# Rev_A.net
KiCad netlist of a schematic drawn in EAGLE
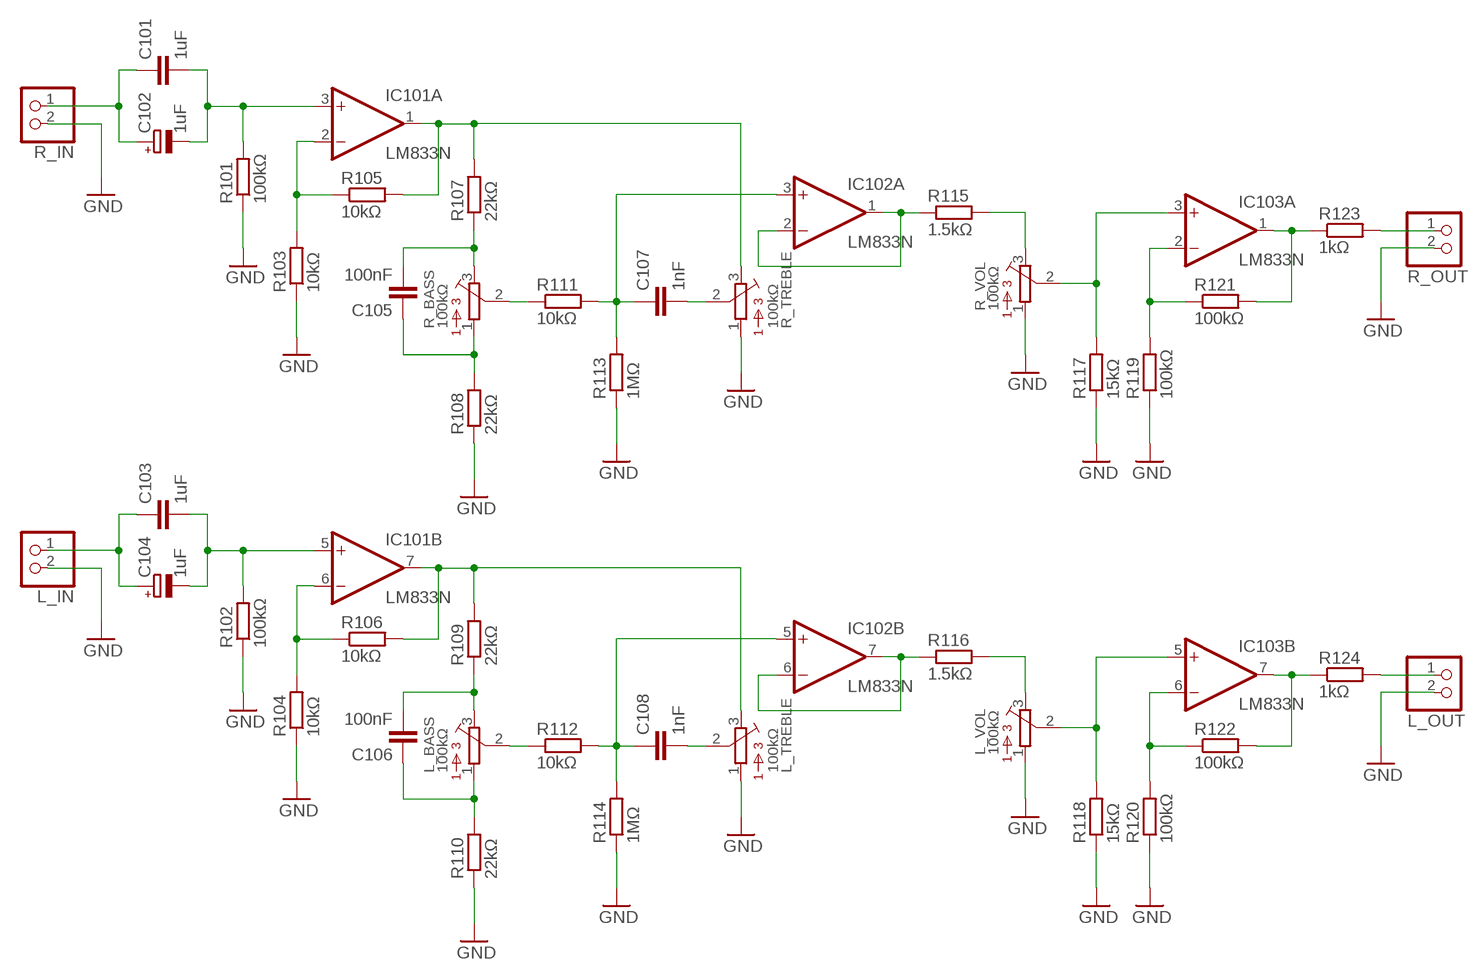
[diagram p0: schematic, sheet 1]
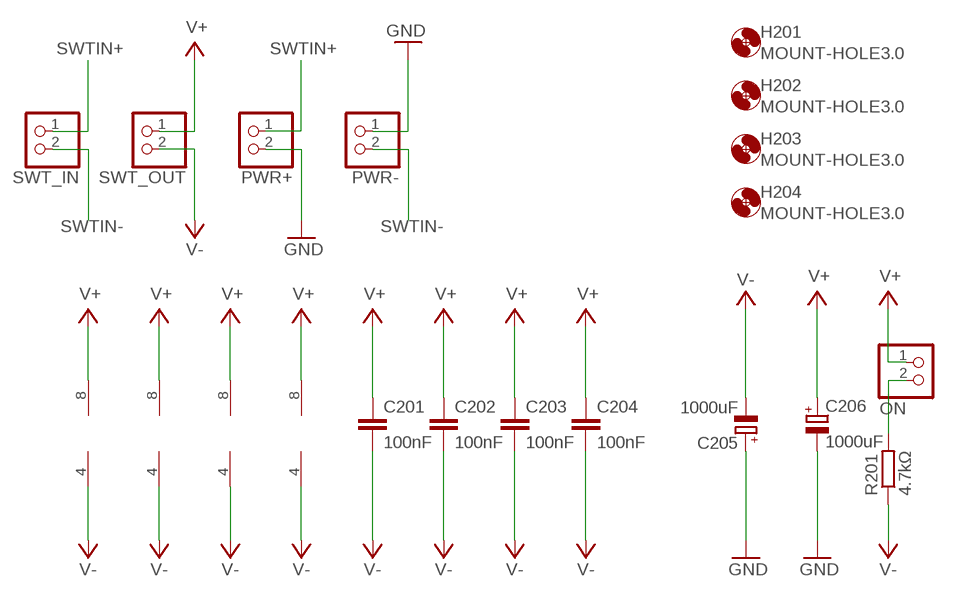
[diagram p1: schematic, sheet 2]
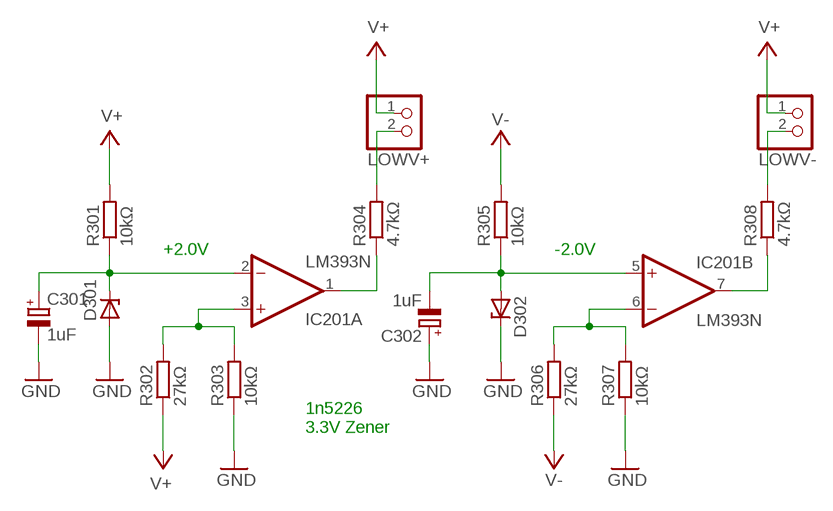
[diagram p2: schematic, sheet 3]

(export (version "E")
  (design (tool "Eeschema 10.0.6"))
  (components
    (comp (ref "C101")
      (value "1uF")
      (footprint "eagle-import:C150-072X183")
      (libsource (lib "eagle-import") (part "C-EU150-072X183"))
    )
    (comp (ref "C102")
      (value "1uF")
      (footprint "eagle-import:E2-5")
      (libsource (lib "eagle-import") (part "CPOL-EUE2-5"))
    )
    (comp (ref "C103")
      (value "1uF")
      (footprint "eagle-import:C150-072X183")
      (libsource (lib "eagle-import") (part "C-EU150-072X183"))
    )
    (comp (ref "C104")
      (value "1uF")
      (footprint "eagle-import:E2-5")
      (libsource (lib "eagle-import") (part "CPOL-EUE2-5"))
    )
    (comp (ref "C105")
      (value "100nF")
      (footprint "eagle-import:C050-025X075")
      (libsource (lib "eagle-import") (part "C-EU050-025X075"))
    )
    (comp (ref "C106")
      (value "100nF")
      (footprint "eagle-import:C050-025X075")
      (libsource (lib "eagle-import") (part "C-EU050-025X075"))
    )
    (comp (ref "C107")
      (value "1nF")
      (footprint "eagle-import:C050-025X075")
      (libsource (lib "eagle-import") (part "C-EU050-025X075"))
    )
    (comp (ref "C108")
      (value "1nF")
      (footprint "eagle-import:C050-025X075")
      (libsource (lib "eagle-import") (part "C-EU050-025X075"))
    )
    (comp (ref "IC101")
      (value "LM833N")
      (footprint "eagle-import:DIL08")
      (libsource (lib "eagle-import") (part "LM833N"))
    )
    (comp (ref "IC102")
      (value "LM833N")
      (footprint "eagle-import:DIL08")
      (libsource (lib "eagle-import") (part "LM833N"))
    )
    (comp (ref "IC103")
      (value "LM833N")
      (footprint "eagle-import:DIL08")
      (libsource (lib "eagle-import") (part "LM833N"))
    )
    (comp (ref "L_BASS")
      (value "100kΩ")
      (footprint "eagle-import:3362U")
      (libsource (lib "eagle-import") (part "3362U"))
    )
    (comp (ref "L_IN")
      (value "JST_2PIN-THM")
      (footprint "eagle-import:JST-PH-2-THM")
      (libsource (lib "eagle-import") (part "JST_2PIN-THM"))
    )
    (comp (ref "L_OUT")
      (value "JST_2PIN-THM")
      (footprint "eagle-import:JST-PH-2-THM")
      (libsource (lib "eagle-import") (part "JST_2PIN-THM"))
    )
    (comp (ref "L_TREBLE")
      (value "100kΩ")
      (footprint "eagle-import:3362U")
      (libsource (lib "eagle-import") (part "3362U"))
    )
    (comp (ref "L_VOL")
      (value "100kΩ")
      (footprint "eagle-import:3362U")
      (libsource (lib "eagle-import") (part "3362U"))
    )
    (comp (ref "R101")
      (value "100kΩ")
      (footprint "eagle-import:0207_10")
      (libsource (lib "eagle-import") (part "R-EU_0207/10"))
    )
    (comp (ref "R102")
      (value "100kΩ")
      (footprint "eagle-import:0207_10")
      (libsource (lib "eagle-import") (part "R-EU_0207/10"))
    )
    (comp (ref "R103")
      (value "10kΩ")
      (footprint "eagle-import:0207_10")
      (libsource (lib "eagle-import") (part "R-EU_0207/10"))
    )
    (comp (ref "R104")
      (value "10kΩ")
      (footprint "eagle-import:0207_10")
      (libsource (lib "eagle-import") (part "R-EU_0207/10"))
    )
    (comp (ref "R105")
      (value "10kΩ")
      (footprint "eagle-import:0207_10")
      (libsource (lib "eagle-import") (part "R-EU_0207/10"))
    )
    (comp (ref "R106")
      (value "10kΩ")
      (footprint "eagle-import:0207_10")
      (libsource (lib "eagle-import") (part "R-EU_0207/10"))
    )
    (comp (ref "R107")
      (value "22kΩ")
      (footprint "eagle-import:0207_10")
      (libsource (lib "eagle-import") (part "R-EU_0207/10"))
    )
    (comp (ref "R108")
      (value "22kΩ")
      (footprint "eagle-import:0207_10")
      (libsource (lib "eagle-import") (part "R-EU_0207/10"))
    )
    (comp (ref "R109")
      (value "22kΩ")
      (footprint "eagle-import:0207_10")
      (libsource (lib "eagle-import") (part "R-EU_0207/10"))
    )
    (comp (ref "R110")
      (value "22kΩ")
      (footprint "eagle-import:0207_10")
      (libsource (lib "eagle-import") (part "R-EU_0207/10"))
    )
    (comp (ref "R111")
      (value "10kΩ")
      (footprint "eagle-import:0207_10")
      (libsource (lib "eagle-import") (part "R-EU_0207/10"))
    )
    (comp (ref "R112")
      (value "10kΩ")
      (footprint "eagle-import:0207_10")
      (libsource (lib "eagle-import") (part "R-EU_0207/10"))
    )
    (comp (ref "R113")
      (value "1MΩ")
      (footprint "eagle-import:0207_10")
      (libsource (lib "eagle-import") (part "R-EU_0207/10"))
    )
    (comp (ref "R114")
      (value "1MΩ")
      (footprint "eagle-import:0207_10")
      (libsource (lib "eagle-import") (part "R-EU_0207/10"))
    )
    (comp (ref "R115")
      (value "1.5kΩ")
      (footprint "eagle-import:0207_10")
      (libsource (lib "eagle-import") (part "R-EU_0207/10"))
    )
    (comp (ref "R116")
      (value "1.5kΩ")
      (footprint "eagle-import:0207_10")
      (libsource (lib "eagle-import") (part "R-EU_0207/10"))
    )
    (comp (ref "R117")
      (value "15kΩ")
      (footprint "eagle-import:0207_10")
      (libsource (lib "eagle-import") (part "R-EU_0207/10"))
    )
    (comp (ref "R118")
      (value "15kΩ")
      (footprint "eagle-import:0207_10")
      (libsource (lib "eagle-import") (part "R-EU_0207/10"))
    )
    (comp (ref "R119")
      (value "100kΩ")
      (footprint "eagle-import:0207_10")
      (libsource (lib "eagle-import") (part "R-EU_0207/10"))
    )
    (comp (ref "R120")
      (value "100kΩ")
      (footprint "eagle-import:0207_10")
      (libsource (lib "eagle-import") (part "R-EU_0207/10"))
    )
    (comp (ref "R121")
      (value "100kΩ")
      (footprint "eagle-import:0207_10")
      (libsource (lib "eagle-import") (part "R-EU_0207/10"))
    )
    (comp (ref "R122")
      (value "100kΩ")
      (footprint "eagle-import:0207_10")
      (libsource (lib "eagle-import") (part "R-EU_0207/10"))
    )
    (comp (ref "R123")
      (value "1kΩ")
      (footprint "eagle-import:0207_10")
      (libsource (lib "eagle-import") (part "R-EU_0207/10"))
    )
    (comp (ref "R124")
      (value "1kΩ")
      (footprint "eagle-import:0207_10")
      (libsource (lib "eagle-import") (part "R-EU_0207/10"))
    )
    (comp (ref "R_BASS")
      (value "100kΩ")
      (footprint "eagle-import:3362U")
      (libsource (lib "eagle-import") (part "3362U"))
    )
    (comp (ref "R_IN")
      (value "JST_2PIN-THM")
      (footprint "eagle-import:JST-PH-2-THM")
      (libsource (lib "eagle-import") (part "JST_2PIN-THM"))
    )
    (comp (ref "R_OUT")
      (value "JST_2PIN-THM")
      (footprint "eagle-import:JST-PH-2-THM")
      (libsource (lib "eagle-import") (part "JST_2PIN-THM"))
    )
    (comp (ref "R_TREBLE")
      (value "100kΩ")
      (footprint "eagle-import:3362U")
      (libsource (lib "eagle-import") (part "3362U"))
    )
    (comp (ref "R_VOL")
      (value "100kΩ")
      (footprint "eagle-import:3362U")
      (libsource (lib "eagle-import") (part "3362U"))
    )
    (comp (ref "C201")
      (value "100nF")
      (footprint "eagle-import:C025-025X050")
      (libsource (lib "eagle-import") (part "C-EU025-025X050"))
    )
    (comp (ref "C202")
      (value "100nF")
      (footprint "eagle-import:C025-025X050")
      (libsource (lib "eagle-import") (part "C-EU025-025X050"))
    )
    (comp (ref "C203")
      (value "100nF")
      (footprint "eagle-import:C025-025X050")
      (libsource (lib "eagle-import") (part "C-EU025-025X050"))
    )
    (comp (ref "C204")
      (value "100nF")
      (footprint "eagle-import:C025-025X050")
      (libsource (lib "eagle-import") (part "C-EU025-025X050"))
    )
    (comp (ref "C205")
      (value "1000uF")
      (footprint "eagle-import:E5-10,5")
      (libsource (lib "eagle-import") (part "CPOL-EUE5-10.5"))
    )
    (comp (ref "C206")
      (value "1000uF")
      (footprint "eagle-import:E5-10,5")
      (libsource (lib "eagle-import") (part "CPOL-EUE5-10.5"))
    )
    (comp (ref "H201")
      (value "MOUNT-HOLE3.0")
      (footprint "eagle-import:3,0")
      (libsource (lib "eagle-import") (part "MOUNT-HOLE3.0"))
    )
    (comp (ref "H202")
      (value "MOUNT-HOLE3.0")
      (footprint "eagle-import:3,0")
      (libsource (lib "eagle-import") (part "MOUNT-HOLE3.0"))
    )
    (comp (ref "H203")
      (value "MOUNT-HOLE3.0")
      (footprint "eagle-import:3,0")
      (libsource (lib "eagle-import") (part "MOUNT-HOLE3.0"))
    )
    (comp (ref "H204")
      (value "MOUNT-HOLE3.0")
      (footprint "eagle-import:3,0")
      (libsource (lib "eagle-import") (part "MOUNT-HOLE3.0"))
    )
    (comp (ref "IC201")
      (value "LM393N")
      (footprint "eagle-import:DIL08")
      (libsource (lib "eagle-import") (part "LM393N"))
    )
    (comp (ref "ON")
      (value "JST_2PIN-THM")
      (footprint "eagle-import:JST-PH-2-THM")
      (libsource (lib "eagle-import") (part "JST_2PIN-THM"))
    )
    (comp (ref "PWR+")
      (value "JST_2PIN-THM")
      (footprint "eagle-import:JST-PH-2-THM")
      (libsource (lib "eagle-import") (part "JST_2PIN-THM"))
    )
    (comp (ref "PWR-")
      (value "JST_2PIN-THM")
      (footprint "eagle-import:JST-PH-2-THM")
      (libsource (lib "eagle-import") (part "JST_2PIN-THM"))
    )
    (comp (ref "R201")
      (value "4.7kΩ")
      (footprint "eagle-import:0207_10")
      (libsource (lib "eagle-import") (part "R-EU_0207/10"))
    )
    (comp (ref "SWT_IN")
      (value "JST_2PIN-THM")
      (footprint "eagle-import:JST-PH-2-THM")
      (libsource (lib "eagle-import") (part "JST_2PIN-THM"))
    )
    (comp (ref "SWT_OUT")
      (value "JST_2PIN-THM")
      (footprint "eagle-import:JST-PH-2-THM")
      (libsource (lib "eagle-import") (part "JST_2PIN-THM"))
    )
    (comp (ref "C301")
      (value "1uF")
      (footprint "eagle-import:E2-5")
      (libsource (lib "eagle-import") (part "CPOL-EUE2-5"))
    )
    (comp (ref "C302")
      (value "1uF")
      (footprint "eagle-import:E2-5")
      (libsource (lib "eagle-import") (part "CPOL-EUE2-5"))
    )
    (comp (ref "D301")
      (value "BZV10")
      (footprint "eagle-import:DO34Z7")
      (libsource (lib "eagle-import") (part "BZV10"))
    )
    (comp (ref "D302")
      (value "BZV10")
      (footprint "eagle-import:DO34Z7")
      (libsource (lib "eagle-import") (part "BZV10"))
    )
    (comp (ref "LOWV+")
      (value "JST_2PIN-THM")
      (footprint "eagle-import:JST-PH-2-THM")
      (libsource (lib "eagle-import") (part "JST_2PIN-THM"))
    )
    (comp (ref "LOWV-")
      (value "JST_2PIN-THM")
      (footprint "eagle-import:JST-PH-2-THM")
      (libsource (lib "eagle-import") (part "JST_2PIN-THM"))
    )
    (comp (ref "R301")
      (value "10kΩ")
      (footprint "eagle-import:0207_10")
      (libsource (lib "eagle-import") (part "R-EU_0207/10"))
    )
    (comp (ref "R302")
      (value "27kΩ")
      (footprint "eagle-import:0207_10")
      (libsource (lib "eagle-import") (part "R-EU_0207/10"))
    )
    (comp (ref "R303")
      (value "10kΩ")
      (footprint "eagle-import:0207_10")
      (libsource (lib "eagle-import") (part "R-EU_0207/10"))
    )
    (comp (ref "R304")
      (value "4.7kΩ")
      (footprint "eagle-import:0207_10")
      (libsource (lib "eagle-import") (part "R-EU_0207/10"))
    )
    (comp (ref "R305")
      (value "10kΩ")
      (footprint "eagle-import:0207_10")
      (libsource (lib "eagle-import") (part "R-EU_0207/10"))
    )
    (comp (ref "R306")
      (value "27kΩ")
      (footprint "eagle-import:0207_10")
      (libsource (lib "eagle-import") (part "R-EU_0207/10"))
    )
    (comp (ref "R307")
      (value "10kΩ")
      (footprint "eagle-import:0207_10")
      (libsource (lib "eagle-import") (part "R-EU_0207/10"))
    )
    (comp (ref "R308")
      (value "4.7kΩ")
      (footprint "eagle-import:0207_10")
      (libsource (lib "eagle-import") (part "R-EU_0207/10"))
    )
  )
  (nets
    (net (code "1") (name "GND") (class "Default")
      (node (ref "C205") (pin "+") (pinfunction "+_+") (pintype "passive"))
      (node (ref "C206") (pin "-") (pinfunction "-_-") (pintype "passive"))
      (node (ref "C301") (pin "-") (pinfunction "-_-") (pintype "passive"))
      (node (ref "C302") (pin "+") (pinfunction "+_+") (pintype "passive"))
      (node (ref "D301") (pin "A") (pinfunction "A_A") (pintype "passive"))
      (node (ref "D302") (pin "C") (pinfunction "C_C") (pintype "passive"))
      (node (ref "L_IN") (pin "2") (pinfunction "1_2") (pintype "passive"))
      (node (ref "L_OUT") (pin "2") (pinfunction "1_2") (pintype "passive"))
      (node (ref "L_TREBLE") (pin "1") (pinfunction "1_1") (pintype "passive"))
      (node (ref "L_VOL") (pin "1") (pinfunction "1_1") (pintype "passive"))
      (node (ref "PWR+") (pin "2") (pinfunction "1_2") (pintype "passive"))
      (node (ref "PWR-") (pin "1") (pinfunction "2_1") (pintype "passive"))
      (node (ref "R101") (pin "1") (pinfunction "1_1") (pintype "passive"))
      (node (ref "R102") (pin "1") (pinfunction "1_1") (pintype "passive"))
      (node (ref "R103") (pin "1") (pinfunction "1_1") (pintype "passive"))
      (node (ref "R104") (pin "1") (pinfunction "1_1") (pintype "passive"))
      (node (ref "R108") (pin "1") (pinfunction "1_1") (pintype "passive"))
      (node (ref "R110") (pin "1") (pinfunction "1_1") (pintype "passive"))
      (node (ref "R113") (pin "1") (pinfunction "1_1") (pintype "passive"))
      (node (ref "R114") (pin "1") (pinfunction "1_1") (pintype "passive"))
      (node (ref "R117") (pin "1") (pinfunction "1_1") (pintype "passive"))
      (node (ref "R118") (pin "1") (pinfunction "1_1") (pintype "passive"))
      (node (ref "R119") (pin "1") (pinfunction "1_1") (pintype "passive"))
      (node (ref "R120") (pin "1") (pinfunction "1_1") (pintype "passive"))
      (node (ref "R303") (pin "1") (pinfunction "1_1") (pintype "passive"))
      (node (ref "R307") (pin "1") (pinfunction "1_1") (pintype "passive"))
      (node (ref "R_IN") (pin "2") (pinfunction "1_2") (pintype "passive"))
      (node (ref "R_OUT") (pin "2") (pinfunction "1_2") (pintype "passive"))
      (node (ref "R_TREBLE") (pin "1") (pinfunction "1_1") (pintype "passive"))
      (node (ref "R_VOL") (pin "1") (pinfunction "1_1") (pintype "passive"))
    )
    (net (code "2") (name "Net-(C105-Pad1)") (class "Default")
      (node (ref "C105") (pin "1") (pinfunction "1_1") (pintype "passive"))
      (node (ref "R108") (pin "2") (pinfunction "2_2") (pintype "passive"))
      (node (ref "R_BASS") (pin "1") (pinfunction "1_1") (pintype "passive"))
    )
    (net (code "3") (name "Net-(C105-Pad2)") (class "Default")
      (node (ref "C105") (pin "2") (pinfunction "2_2") (pintype "passive"))
      (node (ref "R107") (pin "1") (pinfunction "1_1") (pintype "passive"))
      (node (ref "R_BASS") (pin "3") (pinfunction "3_3") (pintype "passive"))
    )
    (net (code "4") (name "Net-(C106-Pad1)") (class "Default")
      (node (ref "C106") (pin "1") (pinfunction "1_1") (pintype "passive"))
      (node (ref "L_BASS") (pin "1") (pinfunction "1_1") (pintype "passive"))
      (node (ref "R110") (pin "2") (pinfunction "2_2") (pintype "passive"))
    )
    (net (code "5") (name "Net-(C106-Pad2)") (class "Default")
      (node (ref "C106") (pin "2") (pinfunction "2_2") (pintype "passive"))
      (node (ref "L_BASS") (pin "3") (pinfunction "3_3") (pintype "passive"))
      (node (ref "R109") (pin "1") (pinfunction "1_1") (pintype "passive"))
    )
    (net (code "6") (name "Net-(C107-Pad2)") (class "Default")
      (node (ref "C107") (pin "2") (pinfunction "2_2") (pintype "passive"))
      (node (ref "R_TREBLE") (pin "2") (pinfunction "2_2") (pintype "passive"))
    )
    (net (code "7") (name "Net-(C108-Pad2)") (class "Default")
      (node (ref "C108") (pin "2") (pinfunction "2_2") (pintype "passive"))
      (node (ref "L_TREBLE") (pin "2") (pinfunction "2_2") (pintype "passive"))
    )
    (net (code "8") (name "Net-(IC101A-+IN)") (class "Default")
      (node (ref "C101") (pin "2") (pinfunction "2_2") (pintype "passive"))
      (node (ref "C102") (pin "-") (pinfunction "-_-") (pintype "passive"))
      (node (ref "IC101") (pin "3") (pinfunction "+IN_3") (pintype "input"))
      (node (ref "R101") (pin "2") (pinfunction "2_2") (pintype "passive"))
    )
    (net (code "9") (name "Net-(IC101A--IN)") (class "Default")
      (node (ref "IC101") (pin "2") (pinfunction "-IN_2") (pintype "input"))
      (node (ref "R103") (pin "2") (pinfunction "2_2") (pintype "passive"))
      (node (ref "R105") (pin "1") (pinfunction "1_1") (pintype "passive"))
    )
    (net (code "10") (name "Net-(IC101A-OUT)") (class "Default")
      (node (ref "IC101") (pin "1") (pinfunction "OUT_1") (pintype "output"))
      (node (ref "R105") (pin "2") (pinfunction "2_2") (pintype "passive"))
      (node (ref "R107") (pin "2") (pinfunction "2_2") (pintype "passive"))
      (node (ref "R_TREBLE") (pin "3") (pinfunction "3_3") (pintype "passive"))
    )
    (net (code "11") (name "Net-(IC101B-+IN)") (class "Default")
      (node (ref "C103") (pin "2") (pinfunction "2_2") (pintype "passive"))
      (node (ref "C104") (pin "-") (pinfunction "-_-") (pintype "passive"))
      (node (ref "IC101") (pin "5") (pinfunction "+IN_5") (pintype "input"))
      (node (ref "R102") (pin "2") (pinfunction "2_2") (pintype "passive"))
    )
    (net (code "12") (name "Net-(IC101B--IN)") (class "Default")
      (node (ref "IC101") (pin "6") (pinfunction "-IN_6") (pintype "input"))
      (node (ref "R104") (pin "2") (pinfunction "2_2") (pintype "passive"))
      (node (ref "R106") (pin "1") (pinfunction "1_1") (pintype "passive"))
    )
    (net (code "13") (name "Net-(IC101B-OUT)") (class "Default")
      (node (ref "IC101") (pin "7") (pinfunction "OUT_7") (pintype "output"))
      (node (ref "L_TREBLE") (pin "3") (pinfunction "3_3") (pintype "passive"))
      (node (ref "R106") (pin "2") (pinfunction "2_2") (pintype "passive"))
      (node (ref "R109") (pin "2") (pinfunction "2_2") (pintype "passive"))
    )
    (net (code "14") (name "Net-(IC102A-+IN)") (class "Default")
      (node (ref "C107") (pin "1") (pinfunction "1_1") (pintype "passive"))
      (node (ref "IC102") (pin "3") (pinfunction "+IN_3") (pintype "input"))
      (node (ref "R111") (pin "2") (pinfunction "2_2") (pintype "passive"))
      (node (ref "R113") (pin "2") (pinfunction "2_2") (pintype "passive"))
    )
    (net (code "15") (name "Net-(IC102A--IN)") (class "Default")
      (node (ref "IC102") (pin "1") (pinfunction "OUT_1") (pintype "output"))
      (node (ref "IC102") (pin "2") (pinfunction "-IN_2") (pintype "input"))
      (node (ref "R115") (pin "1") (pinfunction "1_1") (pintype "passive"))
    )
    (net (code "16") (name "Net-(IC102B-+IN)") (class "Default")
      (node (ref "C108") (pin "1") (pinfunction "1_1") (pintype "passive"))
      (node (ref "IC102") (pin "5") (pinfunction "+IN_5") (pintype "input"))
      (node (ref "R112") (pin "2") (pinfunction "2_2") (pintype "passive"))
      (node (ref "R114") (pin "2") (pinfunction "2_2") (pintype "passive"))
    )
    (net (code "17") (name "Net-(IC102B--IN)") (class "Default")
      (node (ref "IC102") (pin "6") (pinfunction "-IN_6") (pintype "input"))
      (node (ref "IC102") (pin "7") (pinfunction "OUT_7") (pintype "output"))
      (node (ref "R116") (pin "1") (pinfunction "1_1") (pintype "passive"))
    )
    (net (code "18") (name "Net-(IC103A-+IN)") (class "Default")
      (node (ref "IC103") (pin "3") (pinfunction "+IN_3") (pintype "input"))
      (node (ref "R117") (pin "2") (pinfunction "2_2") (pintype "passive"))
      (node (ref "R_VOL") (pin "2") (pinfunction "2_2") (pintype "passive"))
    )
    (net (code "19") (name "Net-(IC103A--IN)") (class "Default")
      (node (ref "IC103") (pin "2") (pinfunction "-IN_2") (pintype "input"))
      (node (ref "R119") (pin "2") (pinfunction "2_2") (pintype "passive"))
      (node (ref "R121") (pin "1") (pinfunction "1_1") (pintype "passive"))
    )
    (net (code "20") (name "Net-(IC103A-OUT)") (class "Default")
      (node (ref "IC103") (pin "1") (pinfunction "OUT_1") (pintype "output"))
      (node (ref "R121") (pin "2") (pinfunction "2_2") (pintype "passive"))
      (node (ref "R123") (pin "1") (pinfunction "1_1") (pintype "passive"))
    )
    (net (code "21") (name "Net-(IC103B-+IN)") (class "Default")
      (node (ref "IC103") (pin "5") (pinfunction "+IN_5") (pintype "input"))
      (node (ref "L_VOL") (pin "2") (pinfunction "2_2") (pintype "passive"))
      (node (ref "R118") (pin "2") (pinfunction "2_2") (pintype "passive"))
    )
    (net (code "22") (name "Net-(IC103B--IN)") (class "Default")
      (node (ref "IC103") (pin "6") (pinfunction "-IN_6") (pintype "input"))
      (node (ref "R120") (pin "2") (pinfunction "2_2") (pintype "passive"))
      (node (ref "R122") (pin "1") (pinfunction "1_1") (pintype "passive"))
    )
    (net (code "23") (name "Net-(IC103B-OUT)") (class "Default")
      (node (ref "IC103") (pin "7") (pinfunction "OUT_7") (pintype "output"))
      (node (ref "R122") (pin "2") (pinfunction "2_2") (pintype "passive"))
      (node (ref "R124") (pin "1") (pinfunction "1_1") (pintype "passive"))
    )
    (net (code "24") (name "Net-(IC201A-+IN)") (class "Default")
      (node (ref "IC201") (pin "3") (pinfunction "+IN_3") (pintype "input"))
      (node (ref "R302") (pin "2") (pinfunction "2_2") (pintype "passive"))
      (node (ref "R303") (pin "2") (pinfunction "2_2") (pintype "passive"))
    )
    (net (code "25") (name "Net-(IC201A--IN)") (class "Default")
      (node (ref "C301") (pin "+") (pinfunction "+_+") (pintype "passive"))
      (node (ref "D301") (pin "C") (pinfunction "C_C") (pintype "passive"))
      (node (ref "IC201") (pin "2") (pinfunction "-IN_2") (pintype "input"))
      (node (ref "R301") (pin "1") (pinfunction "1_1") (pintype "passive"))
    )
    (net (code "26") (name "Net-(IC201A-OUT)") (class "Default")
      (node (ref "IC201") (pin "1") (pinfunction "OUT_1") (pintype "output"))
      (node (ref "R304") (pin "1") (pinfunction "1_1") (pintype "passive"))
    )
    (net (code "27") (name "Net-(IC201B-+IN)") (class "Default")
      (node (ref "C302") (pin "-") (pinfunction "-_-") (pintype "passive"))
      (node (ref "D302") (pin "A") (pinfunction "A_A") (pintype "passive"))
      (node (ref "IC201") (pin "5") (pinfunction "+IN_5") (pintype "input"))
      (node (ref "R305") (pin "1") (pinfunction "1_1") (pintype "passive"))
    )
    (net (code "28") (name "Net-(IC201B--IN)") (class "Default")
      (node (ref "IC201") (pin "6") (pinfunction "-IN_6") (pintype "input"))
      (node (ref "R306") (pin "2") (pinfunction "2_2") (pintype "passive"))
      (node (ref "R307") (pin "2") (pinfunction "2_2") (pintype "passive"))
    )
    (net (code "29") (name "Net-(IC201B-OUT)") (class "Default")
      (node (ref "IC201") (pin "7") (pinfunction "OUT_7") (pintype "output"))
      (node (ref "R308") (pin "1") (pinfunction "1_1") (pintype "passive"))
    )
    (net (code "30") (name "Net-(LOWV+-1)") (class "Default")
      (node (ref "LOWV+") (pin "2") (pinfunction "1_2") (pintype "passive"))
      (node (ref "R304") (pin "2") (pinfunction "2_2") (pintype "passive"))
    )
    (net (code "31") (name "Net-(LOWV--1)") (class "Default")
      (node (ref "LOWV-") (pin "2") (pinfunction "1_2") (pintype "passive"))
      (node (ref "R308") (pin "2") (pinfunction "2_2") (pintype "passive"))
    )
    (net (code "32") (name "Net-(L_BASS-Pad2)") (class "Default")
      (node (ref "L_BASS") (pin "2") (pinfunction "2_2") (pintype "passive"))
      (node (ref "R112") (pin "1") (pinfunction "1_1") (pintype "passive"))
    )
    (net (code "33") (name "Net-(L_IN-2)") (class "Default")
      (node (ref "C103") (pin "1") (pinfunction "1_1") (pintype "passive"))
      (node (ref "C104") (pin "+") (pinfunction "+_+") (pintype "passive"))
      (node (ref "L_IN") (pin "1") (pinfunction "2_1") (pintype "passive"))
    )
    (net (code "34") (name "Net-(L_OUT-2)") (class "Default")
      (node (ref "L_OUT") (pin "1") (pinfunction "2_1") (pintype "passive"))
      (node (ref "R124") (pin "2") (pinfunction "2_2") (pintype "passive"))
    )
    (net (code "35") (name "Net-(L_VOL-Pad3)") (class "Default")
      (node (ref "L_VOL") (pin "3") (pinfunction "3_3") (pintype "passive"))
      (node (ref "R116") (pin "2") (pinfunction "2_2") (pintype "passive"))
    )
    (net (code "36") (name "Net-(ON-1)") (class "Default")
      (node (ref "ON") (pin "2") (pinfunction "1_2") (pintype "passive"))
      (node (ref "R201") (pin "2") (pinfunction "2_2") (pintype "passive"))
    )
    (net (code "37") (name "Net-(R111-Pad1)") (class "Default")
      (node (ref "R111") (pin "1") (pinfunction "1_1") (pintype "passive"))
      (node (ref "R_BASS") (pin "2") (pinfunction "2_2") (pintype "passive"))
    )
    (net (code "38") (name "Net-(R115-Pad2)") (class "Default")
      (node (ref "R115") (pin "2") (pinfunction "2_2") (pintype "passive"))
      (node (ref "R_VOL") (pin "3") (pinfunction "3_3") (pintype "passive"))
    )
    (net (code "39") (name "Net-(R_IN-2)") (class "Default")
      (node (ref "C101") (pin "1") (pinfunction "1_1") (pintype "passive"))
      (node (ref "C102") (pin "+") (pinfunction "+_+") (pintype "passive"))
      (node (ref "R_IN") (pin "1") (pinfunction "2_1") (pintype "passive"))
    )
    (net (code "40") (name "Net-(R_OUT-2)") (class "Default")
      (node (ref "R123") (pin "2") (pinfunction "2_2") (pintype "passive"))
      (node (ref "R_OUT") (pin "1") (pinfunction "2_1") (pintype "passive"))
    )
    (net (code "41") (name "SWTIN+") (class "Default")
      (node (ref "PWR+") (pin "1") (pinfunction "2_1") (pintype "passive"))
      (node (ref "SWT_IN") (pin "1") (pinfunction "2_1") (pintype "passive"))
    )
    (net (code "42") (name "SWTIN-") (class "Default")
      (node (ref "PWR-") (pin "2") (pinfunction "1_2") (pintype "passive"))
      (node (ref "SWT_IN") (pin "2") (pinfunction "1_2") (pintype "passive"))
    )
    (net (code "43") (name "V+") (class "Default")
      (node (ref "C201") (pin "1") (pinfunction "1_1") (pintype "passive"))
      (node (ref "C202") (pin "1") (pinfunction "1_1") (pintype "passive"))
      (node (ref "C203") (pin "1") (pinfunction "1_1") (pintype "passive"))
      (node (ref "C204") (pin "1") (pinfunction "1_1") (pintype "passive"))
      (node (ref "C206") (pin "+") (pinfunction "+_+") (pintype "passive"))
      (node (ref "IC101") (pin "8") (pinfunction "V+_8") (pintype "power_in"))
      (node (ref "IC102") (pin "8") (pinfunction "V+_8") (pintype "power_in"))
      (node (ref "IC103") (pin "8") (pinfunction "V+_8") (pintype "power_in"))
      (node (ref "IC201") (pin "8") (pinfunction "V+_8") (pintype "power_in"))
      (node (ref "LOWV+") (pin "1") (pinfunction "2_1") (pintype "passive"))
      (node (ref "LOWV-") (pin "1") (pinfunction "2_1") (pintype "passive"))
      (node (ref "ON") (pin "1") (pinfunction "2_1") (pintype "passive"))
      (node (ref "R301") (pin "2") (pinfunction "2_2") (pintype "passive"))
      (node (ref "R302") (pin "1") (pinfunction "1_1") (pintype "passive"))
      (node (ref "SWT_OUT") (pin "1") (pinfunction "2_1") (pintype "passive"))
    )
    (net (code "44") (name "V-") (class "Default")
      (node (ref "C201") (pin "2") (pinfunction "2_2") (pintype "passive"))
      (node (ref "C202") (pin "2") (pinfunction "2_2") (pintype "passive"))
      (node (ref "C203") (pin "2") (pinfunction "2_2") (pintype "passive"))
      (node (ref "C204") (pin "2") (pinfunction "2_2") (pintype "passive"))
      (node (ref "C205") (pin "-") (pinfunction "-_-") (pintype "passive"))
      (node (ref "IC101") (pin "4") (pinfunction "V-_4") (pintype "power_in"))
      (node (ref "IC102") (pin "4") (pinfunction "V-_4") (pintype "power_in"))
      (node (ref "IC103") (pin "4") (pinfunction "V-_4") (pintype "power_in"))
      (node (ref "IC201") (pin "4") (pinfunction "V-_4") (pintype "power_in"))
      (node (ref "R201") (pin "1") (pinfunction "1_1") (pintype "passive"))
      (node (ref "R305") (pin "2") (pinfunction "2_2") (pintype "passive"))
      (node (ref "R306") (pin "1") (pinfunction "1_1") (pintype "passive"))
      (node (ref "SWT_OUT") (pin "2") (pinfunction "1_2") (pintype "passive"))
    )
  )
)
